# robotito.net
KiCad netlist of a schematic drawn in EAGLE
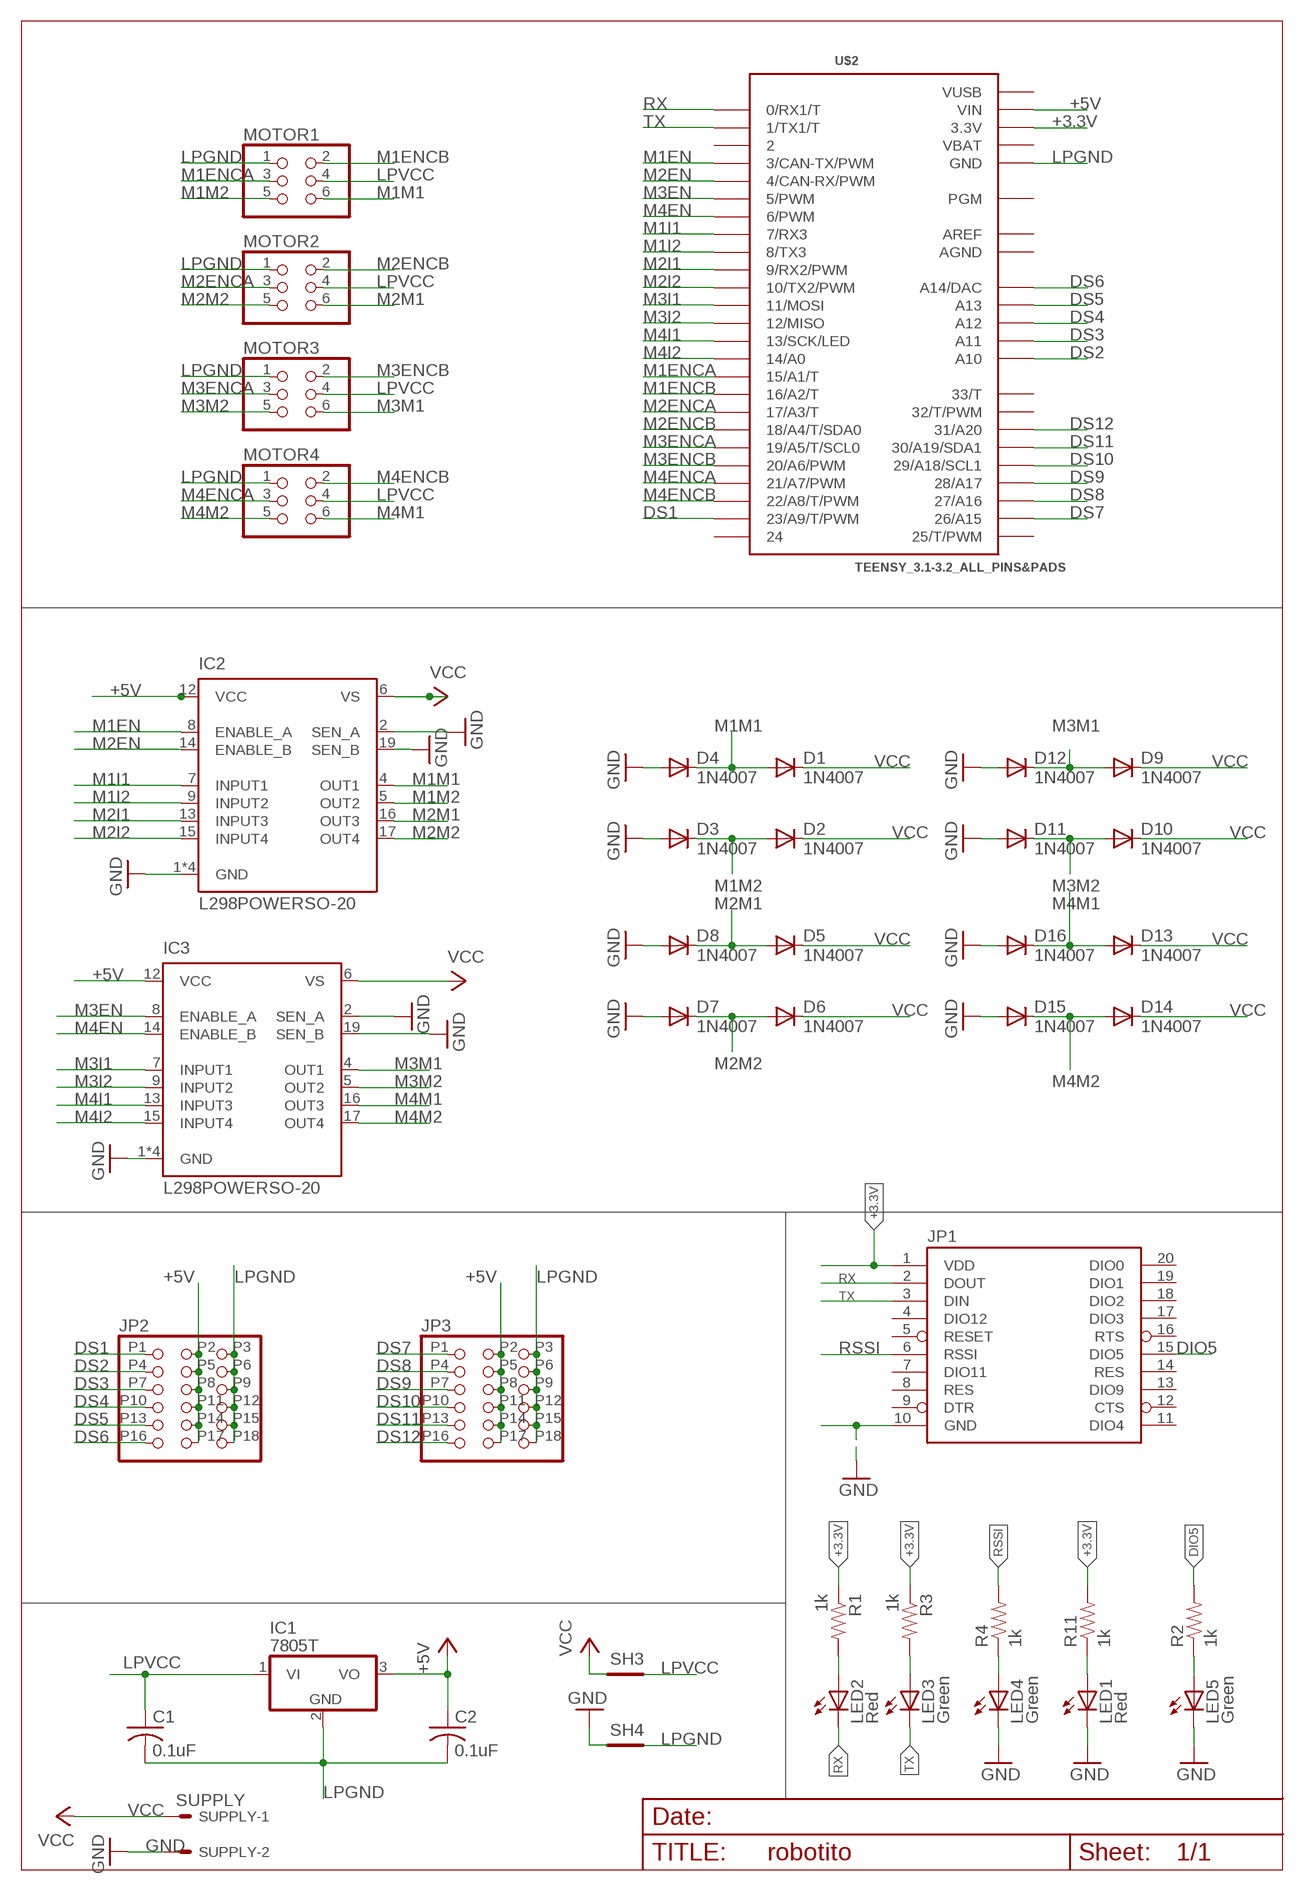
[diagram p0: schematic, sheet 1]

(export (version "E")
  (design (tool "Eeschema 10.0.6"))
  (components
    (comp (ref "C1")
      (value "0.1uF")
      (footprint "eagle-import:C0805")
      (libsource (lib "eagle-import") (part "C-USC0805"))
    )
    (comp (ref "C2")
      (value "0.1uF")
      (footprint "eagle-import:C0805")
      (libsource (lib "eagle-import") (part "C-USC0805"))
    )
    (comp (ref "D1")
      (value "1N4007")
      (footprint "eagle-import:DO41-10")
      (libsource (lib "eagle-import") (part "1N4004"))
    )
    (comp (ref "D2")
      (value "1N4007")
      (footprint "eagle-import:DO41-10")
      (libsource (lib "eagle-import") (part "1N4004"))
    )
    (comp (ref "D3")
      (value "1N4007")
      (footprint "eagle-import:DO41-10")
      (libsource (lib "eagle-import") (part "1N4004"))
    )
    (comp (ref "D4")
      (value "1N4007")
      (footprint "eagle-import:DO41-10")
      (libsource (lib "eagle-import") (part "1N4004"))
    )
    (comp (ref "D5")
      (value "1N4007")
      (footprint "eagle-import:DO41-10")
      (libsource (lib "eagle-import") (part "1N4004"))
    )
    (comp (ref "D6")
      (value "1N4007")
      (footprint "eagle-import:DO41-10")
      (libsource (lib "eagle-import") (part "1N4004"))
    )
    (comp (ref "D7")
      (value "1N4007")
      (footprint "eagle-import:DO41-10")
      (libsource (lib "eagle-import") (part "1N4004"))
    )
    (comp (ref "D8")
      (value "1N4007")
      (footprint "eagle-import:DO41-10")
      (libsource (lib "eagle-import") (part "1N4004"))
    )
    (comp (ref "D9")
      (value "1N4007")
      (footprint "eagle-import:DO41-10")
      (libsource (lib "eagle-import") (part "1N4004"))
    )
    (comp (ref "D10")
      (value "1N4007")
      (footprint "eagle-import:DO41-10")
      (libsource (lib "eagle-import") (part "1N4004"))
    )
    (comp (ref "D11")
      (value "1N4007")
      (footprint "eagle-import:DO41-10")
      (libsource (lib "eagle-import") (part "1N4004"))
    )
    (comp (ref "D12")
      (value "1N4007")
      (footprint "eagle-import:DO41-10")
      (libsource (lib "eagle-import") (part "1N4004"))
    )
    (comp (ref "D13")
      (value "1N4007")
      (footprint "eagle-import:DO41-10")
      (libsource (lib "eagle-import") (part "1N4004"))
    )
    (comp (ref "D14")
      (value "1N4007")
      (footprint "eagle-import:DO41-10")
      (libsource (lib "eagle-import") (part "1N4004"))
    )
    (comp (ref "D15")
      (value "1N4007")
      (footprint "eagle-import:DO41-10")
      (libsource (lib "eagle-import") (part "1N4004"))
    )
    (comp (ref "D16")
      (value "1N4007")
      (footprint "eagle-import:DO41-10")
      (libsource (lib "eagle-import") (part "1N4004"))
    )
    (comp (ref "IC1")
      (value "7805T")
      (footprint "eagle-import:TO220H")
      (libsource (lib "eagle-import") (part "78T05"))
    )
    (comp (ref "IC2")
      (value "L298POWERSO-20")
      (footprint "eagle-import:POWERSO-20")
      (libsource (lib "eagle-import") (part "L298POWERSO-20"))
    )
    (comp (ref "IC3")
      (value "L298POWERSO-20")
      (footprint "eagle-import:POWERSO-20")
      (libsource (lib "eagle-import") (part "L298POWERSO-20"))
    )
    (comp (ref "JP1")
      (value "XBEE-1B1")
      (footprint "eagle-import:XBEE-1")
      (libsource (lib "eagle-import") (part "XBEE-1B1"))
    )
    (comp (ref "JP2")
      (value "PINHD-2X6")
      (footprint "eagle-import:2X06")
      (libsource (lib "eagle-import") (part "PINHD-2X6"))
    )
    (comp (ref "JP3")
      (value "PINHD-2X6")
      (footprint "eagle-import:2X06")
      (libsource (lib "eagle-import") (part "PINHD-2X6"))
    )
    (comp (ref "LED1")
      (value "Red")
      (footprint "eagle-import:LED-0603")
      (libsource (lib "eagle-import") (part "LED-RED0603"))
    )
    (comp (ref "LED2")
      (value "Red")
      (footprint "eagle-import:LED-0603")
      (libsource (lib "eagle-import") (part "LED-RED0603"))
    )
    (comp (ref "LED3")
      (value "Green")
      (footprint "eagle-import:LED-0603")
      (libsource (lib "eagle-import") (part "LED-GREEN0603"))
    )
    (comp (ref "LED4")
      (value "Green")
      (footprint "eagle-import:LED-0603")
      (libsource (lib "eagle-import") (part "LED-GREEN0603"))
    )
    (comp (ref "LED5")
      (value "Green")
      (footprint "eagle-import:LED-0603")
      (libsource (lib "eagle-import") (part "LED-GREEN0603"))
    )
    (comp (ref "MOTOR1")
      (value "PINHD-2X3")
      (footprint "eagle-import:2X03")
      (libsource (lib "eagle-import") (part "PINHD-2X3"))
    )
    (comp (ref "MOTOR2")
      (value "PINHD-2X3")
      (footprint "eagle-import:2X03")
      (libsource (lib "eagle-import") (part "PINHD-2X3"))
    )
    (comp (ref "MOTOR3")
      (value "PINHD-2X3")
      (footprint "eagle-import:2X03")
      (libsource (lib "eagle-import") (part "PINHD-2X3"))
    )
    (comp (ref "MOTOR4")
      (value "PINHD-2X3")
      (footprint "eagle-import:2X03")
      (libsource (lib "eagle-import") (part "PINHD-2X3"))
    )
    (comp (ref "R1")
      (value "1k")
      (footprint "eagle-import:0603-RES")
      (libsource (lib "eagle-import") (part "1KOHM1/10W1%(0603)"))
    )
    (comp (ref "R2")
      (value "1k")
      (footprint "eagle-import:0603-RES")
      (libsource (lib "eagle-import") (part "1KOHM1/10W1%(0603)"))
    )
    (comp (ref "R3")
      (value "1k")
      (footprint "eagle-import:0603-RES")
      (libsource (lib "eagle-import") (part "1KOHM1/10W1%(0603)"))
    )
    (comp (ref "R4")
      (value "1k")
      (footprint "eagle-import:0603-RES")
      (libsource (lib "eagle-import") (part "1KOHM1/10W1%(0603)"))
    )
    (comp (ref "R11")
      (value "1k")
      (footprint "eagle-import:0603-RES")
      (libsource (lib "eagle-import") (part "1KOHM1/10W1%(0603)"))
    )
    (comp (ref "SH3")
      (value "SHORT-HT5")
      (footprint "eagle-import:SHORT_TOP-50")
      (libsource (lib "eagle-import") (part "SHORT-HT5"))
    )
    (comp (ref "SH4")
      (value "SHORT-HT5")
      (footprint "eagle-import:SHORT_TOP-50")
      (libsource (lib "eagle-import") (part "SHORT-HT5"))
    )
    (comp (ref "SUPPLY")
      (value "SUPPLY")
      (footprint "eagle-import:6410-02")
      (libsource (lib "eagle-import") (part "22-?-0227-2021"))
    )
    (comp (ref "U$2")
      (value "TEENSY_3.1-3.2_ALL_PINS&PADS")
      (footprint "eagle-import:TEENSY_3.0-3.2_ALL_PINS_&_PADS")
      (libsource (lib "eagle-import") (part "TEENSY_3.1-3.2_ALL_PINS&PADS"))
    )
  )
  (nets
    (net (code "1") (name "+3.3V") (class "Default")
      (node (ref "JP1") (pin "1") (pinfunction "VDD_1") (pintype "power_in"))
      (node (ref "R1") (pin "1") (pinfunction "1_1") (pintype "passive"))
      (node (ref "R11") (pin "2") (pinfunction "2_2") (pintype "passive"))
      (node (ref "R3") (pin "1") (pinfunction "1_1") (pintype "passive"))
      (node (ref "U$2") (pin "3.3V") (pinfunction "3.3V_3.3V") (pintype "power_in"))
      (node (ref "U$2") (pin "3.3V1") (pinfunction "3.3V_3.3V1") (pintype "power_in"))
      (node (ref "U$2") (pin "3.3V2") (pinfunction "3.3V_3.3V2") (pintype "power_in"))
    )
    (net (code "2") (name "+5V") (class "Default")
      (node (ref "C2") (pin "1") (pinfunction "1_1") (pintype "passive"))
      (node (ref "IC1") (pin "3") (pinfunction "VO_3") (pintype "passive"))
      (node (ref "IC2") (pin "12") (pinfunction "VCC_12") (pintype "power_in"))
      (node (ref "IC3") (pin "12") (pinfunction "VCC_12") (pintype "power_in"))
      (node (ref "JP2") (pin "P11") (pinfunction "P11_P11") (pintype "passive"))
      (node (ref "JP2") (pin "P14") (pinfunction "P14_P14") (pintype "passive"))
      (node (ref "JP2") (pin "P17") (pinfunction "P17_P17") (pintype "passive"))
      (node (ref "JP2") (pin "P2") (pinfunction "P2_P2") (pintype "passive"))
      (node (ref "JP2") (pin "P5") (pinfunction "P5_P5") (pintype "passive"))
      (node (ref "JP2") (pin "P8") (pinfunction "P8_P8") (pintype "passive"))
      (node (ref "JP3") (pin "P11") (pinfunction "P11_P11") (pintype "passive"))
      (node (ref "JP3") (pin "P14") (pinfunction "P14_P14") (pintype "passive"))
      (node (ref "JP3") (pin "P17") (pinfunction "P17_P17") (pintype "passive"))
      (node (ref "JP3") (pin "P2") (pinfunction "P2_P2") (pintype "passive"))
      (node (ref "JP3") (pin "P5") (pinfunction "P5_P5") (pintype "passive"))
      (node (ref "JP3") (pin "P8") (pinfunction "P8_P8") (pintype "passive"))
      (node (ref "U$2") (pin "VIN") (pinfunction "VIN_VIN") (pintype "power_in"))
    )
    (net (code "3") (name "/AGND") (class "Default")
      (node (ref "U$2") (pin "AGND") (pinfunction "AGND_AGND") (pintype "power_in"))
    )
    (net (code "4") (name "/AREF") (class "Default")
      (node (ref "U$2") (pin "AREF") (pinfunction "AREF_AREF") (pintype "power_in"))
    )
    (net (code "5") (name "/DS1") (class "Default")
      (node (ref "JP2") (pin "P1") (pinfunction "P1_P1") (pintype "passive"))
      (node (ref "U$2") (pin "23/A9") (pinfunction "23/A9/T/PWM_23/A9") (pintype "bidirectional"))
    )
    (net (code "6") (name "/DS2") (class "Default")
      (node (ref "JP2") (pin "P4") (pinfunction "P4_P4") (pintype "passive"))
      (node (ref "U$2") (pin "A10") (pinfunction "A10_A10") (pintype "bidirectional"))
    )
    (net (code "7") (name "/DS3") (class "Default")
      (node (ref "JP2") (pin "P7") (pinfunction "P7_P7") (pintype "passive"))
      (node (ref "U$2") (pin "A11") (pinfunction "A11_A11") (pintype "bidirectional"))
    )
    (net (code "8") (name "/DS4") (class "Default")
      (node (ref "JP2") (pin "P10") (pinfunction "P10_P10") (pintype "passive"))
      (node (ref "U$2") (pin "A12") (pinfunction "A12_A12") (pintype "bidirectional"))
    )
    (net (code "9") (name "/DS5") (class "Default")
      (node (ref "JP2") (pin "P13") (pinfunction "P13_P13") (pintype "passive"))
      (node (ref "U$2") (pin "A13") (pinfunction "A13_A13") (pintype "bidirectional"))
    )
    (net (code "10") (name "/DS6") (class "Default")
      (node (ref "JP2") (pin "P16") (pinfunction "P16_P16") (pintype "passive"))
      (node (ref "U$2") (pin "RESET/DAC") (pinfunction "A14/DAC_RESET/DAC") (pintype "bidirectional"))
    )
    (net (code "11") (name "/DS7") (class "Default")
      (node (ref "JP3") (pin "P1") (pinfunction "P1_P1") (pintype "passive"))
      (node (ref "U$2") (pin "26") (pinfunction "26/A15_26") (pintype "bidirectional"))
    )
    (net (code "12") (name "/DS8") (class "Default")
      (node (ref "JP3") (pin "P4") (pinfunction "P4_P4") (pintype "passive"))
      (node (ref "U$2") (pin "27") (pinfunction "27/A16_27") (pintype "bidirectional"))
    )
    (net (code "13") (name "/DS9") (class "Default")
      (node (ref "JP3") (pin "P7") (pinfunction "P7_P7") (pintype "passive"))
      (node (ref "U$2") (pin "28") (pinfunction "28/A17_28") (pintype "bidirectional"))
    )
    (net (code "14") (name "/DS10") (class "Default")
      (node (ref "JP3") (pin "P10") (pinfunction "P10_P10") (pintype "passive"))
      (node (ref "U$2") (pin "29") (pinfunction "29/A18/SCL1_29") (pintype "bidirectional"))
    )
    (net (code "15") (name "/DS11") (class "Default")
      (node (ref "JP3") (pin "P13") (pinfunction "P13_P13") (pintype "passive"))
      (node (ref "U$2") (pin "30") (pinfunction "30/A19/SDA1_30") (pintype "bidirectional"))
    )
    (net (code "16") (name "/DS12") (class "Default")
      (node (ref "JP3") (pin "P16") (pinfunction "P16_P16") (pintype "passive"))
      (node (ref "U$2") (pin "31") (pinfunction "31/A20_31") (pintype "bidirectional"))
    )
    (net (code "17") (name "/LPGND") (class "Default")
      (node (ref "C1") (pin "2") (pinfunction "2_2") (pintype "passive"))
      (node (ref "C2") (pin "2") (pinfunction "2_2") (pintype "passive"))
      (node (ref "IC1") (pin "2") (pinfunction "GND_2") (pintype "passive"))
      (node (ref "JP2") (pin "P12") (pinfunction "P12_P12") (pintype "passive"))
      (node (ref "JP2") (pin "P15") (pinfunction "P15_P15") (pintype "passive"))
      (node (ref "JP2") (pin "P18") (pinfunction "P18_P18") (pintype "passive"))
      (node (ref "JP2") (pin "P3") (pinfunction "P3_P3") (pintype "passive"))
      (node (ref "JP2") (pin "P6") (pinfunction "P6_P6") (pintype "passive"))
      (node (ref "JP2") (pin "P9") (pinfunction "P9_P9") (pintype "passive"))
      (node (ref "JP3") (pin "P12") (pinfunction "P12_P12") (pintype "passive"))
      (node (ref "JP3") (pin "P15") (pinfunction "P15_P15") (pintype "passive"))
      (node (ref "JP3") (pin "P18") (pinfunction "P18_P18") (pintype "passive"))
      (node (ref "JP3") (pin "P3") (pinfunction "P3_P3") (pintype "passive"))
      (node (ref "JP3") (pin "P6") (pinfunction "P6_P6") (pintype "passive"))
      (node (ref "JP3") (pin "P9") (pinfunction "P9_P9") (pintype "passive"))
      (node (ref "MOTOR1") (pin "1") (pinfunction "1_1") (pintype "passive"))
      (node (ref "MOTOR2") (pin "1") (pinfunction "1_1") (pintype "passive"))
      (node (ref "MOTOR3") (pin "1") (pinfunction "1_1") (pintype "passive"))
      (node (ref "MOTOR4") (pin "1") (pinfunction "1_1") (pintype "passive"))
      (node (ref "SH4") (pin "2") (pinfunction "P$2_2") (pintype "bidirectional"))
      (node (ref "U$2") (pin "GND") (pinfunction "GND_GND") (pintype "power_in"))
      (node (ref "U$2") (pin "GND1") (pinfunction "GND_GND1") (pintype "power_in"))
      (node (ref "U$2") (pin "GND2") (pinfunction "GND_GND2") (pintype "power_in"))
    )
    (net (code "18") (name "/LPVCC") (class "Default")
      (node (ref "C1") (pin "1") (pinfunction "1_1") (pintype "passive"))
      (node (ref "IC1") (pin "1") (pinfunction "VI_1") (pintype "input"))
      (node (ref "MOTOR1") (pin "4") (pinfunction "4_4") (pintype "passive"))
      (node (ref "MOTOR2") (pin "4") (pinfunction "4_4") (pintype "passive"))
      (node (ref "MOTOR3") (pin "4") (pinfunction "4_4") (pintype "passive"))
      (node (ref "MOTOR4") (pin "4") (pinfunction "4_4") (pintype "passive"))
      (node (ref "SH3") (pin "2") (pinfunction "P$2_2") (pintype "bidirectional"))
    )
    (net (code "19") (name "/M1EN") (class "Default")
      (node (ref "IC2") (pin "8") (pinfunction "ENABLE_A_8") (pintype "input"))
      (node (ref "U$2") (pin "3") (pinfunction "3/CAN-TX/PWM_3") (pintype "bidirectional"))
    )
    (net (code "20") (name "/M1ENCA") (class "Default")
      (node (ref "MOTOR1") (pin "3") (pinfunction "3_3") (pintype "passive"))
      (node (ref "U$2") (pin "15/A1") (pinfunction "15/A1/T_15/A1") (pintype "bidirectional"))
    )
    (net (code "21") (name "/M1ENCB") (class "Default")
      (node (ref "MOTOR1") (pin "2") (pinfunction "2_2") (pintype "passive"))
      (node (ref "U$2") (pin "16/A2") (pinfunction "16/A2/T_16/A2") (pintype "bidirectional"))
    )
    (net (code "22") (name "/M1I1") (class "Default")
      (node (ref "IC2") (pin "7") (pinfunction "INPUT1_7") (pintype "input"))
      (node (ref "U$2") (pin "7") (pinfunction "7/RX3_7") (pintype "bidirectional"))
    )
    (net (code "23") (name "/M1I2") (class "Default")
      (node (ref "IC2") (pin "9") (pinfunction "INPUT2_9") (pintype "input"))
      (node (ref "U$2") (pin "8") (pinfunction "8/TX3_8") (pintype "bidirectional"))
    )
    (net (code "24") (name "/M1M1") (class "Default")
      (node (ref "D1") (pin "A") (pinfunction "A_A") (pintype "passive"))
      (node (ref "D4") (pin "C") (pinfunction "C_C") (pintype "passive"))
      (node (ref "IC2") (pin "4") (pinfunction "OUT1_4") (pintype "output"))
      (node (ref "MOTOR1") (pin "6") (pinfunction "6_6") (pintype "passive"))
    )
    (net (code "25") (name "/M1M2") (class "Default")
      (node (ref "D2") (pin "A") (pinfunction "A_A") (pintype "passive"))
      (node (ref "D3") (pin "C") (pinfunction "C_C") (pintype "passive"))
      (node (ref "IC2") (pin "5") (pinfunction "OUT2_5") (pintype "output"))
      (node (ref "MOTOR1") (pin "5") (pinfunction "5_5") (pintype "passive"))
    )
    (net (code "26") (name "/M2EN") (class "Default")
      (node (ref "IC2") (pin "14") (pinfunction "ENABLE_B_14") (pintype "input"))
      (node (ref "U$2") (pin "4") (pinfunction "4/CAN-RX/PWM_4") (pintype "bidirectional"))
    )
    (net (code "27") (name "/M2ENCA") (class "Default")
      (node (ref "MOTOR2") (pin "3") (pinfunction "3_3") (pintype "passive"))
      (node (ref "U$2") (pin "17/A3") (pinfunction "17/A3/T_17/A3") (pintype "bidirectional"))
    )
    (net (code "28") (name "/M2ENCB") (class "Default")
      (node (ref "MOTOR2") (pin "2") (pinfunction "2_2") (pintype "passive"))
      (node (ref "U$2") (pin "18/A4") (pinfunction "18/A4/T/SDA0_18/A4") (pintype "bidirectional"))
    )
    (net (code "29") (name "/M2I1") (class "Default")
      (node (ref "IC2") (pin "13") (pinfunction "INPUT3_13") (pintype "input"))
      (node (ref "U$2") (pin "9") (pinfunction "9/RX2/PWM_9") (pintype "bidirectional"))
    )
    (net (code "30") (name "/M2I2") (class "Default")
      (node (ref "IC2") (pin "15") (pinfunction "INPUT4_15") (pintype "input"))
      (node (ref "U$2") (pin "10") (pinfunction "10/TX2/PWM_10") (pintype "bidirectional"))
    )
    (net (code "31") (name "/M2M1") (class "Default")
      (node (ref "D5") (pin "A") (pinfunction "A_A") (pintype "passive"))
      (node (ref "D8") (pin "C") (pinfunction "C_C") (pintype "passive"))
      (node (ref "IC2") (pin "16") (pinfunction "OUT3_16") (pintype "output"))
      (node (ref "MOTOR2") (pin "6") (pinfunction "6_6") (pintype "passive"))
    )
    (net (code "32") (name "/M2M2") (class "Default")
      (node (ref "D6") (pin "A") (pinfunction "A_A") (pintype "passive"))
      (node (ref "D7") (pin "C") (pinfunction "C_C") (pintype "passive"))
      (node (ref "IC2") (pin "17") (pinfunction "OUT4_17") (pintype "output"))
      (node (ref "MOTOR2") (pin "5") (pinfunction "5_5") (pintype "passive"))
    )
    (net (code "33") (name "/M3EN") (class "Default")
      (node (ref "IC3") (pin "8") (pinfunction "ENABLE_A_8") (pintype "input"))
      (node (ref "U$2") (pin "5") (pinfunction "5/PWM_5") (pintype "bidirectional"))
    )
    (net (code "34") (name "/M3ENCA") (class "Default")
      (node (ref "MOTOR3") (pin "3") (pinfunction "3_3") (pintype "passive"))
      (node (ref "U$2") (pin "19/A5") (pinfunction "19/A5/T/SCL0_19/A5") (pintype "bidirectional"))
    )
    (net (code "35") (name "/M3ENCB") (class "Default")
      (node (ref "MOTOR3") (pin "2") (pinfunction "2_2") (pintype "passive"))
      (node (ref "U$2") (pin "20/A6") (pinfunction "20/A6/PWM_20/A6") (pintype "bidirectional"))
    )
    (net (code "36") (name "/M3I1") (class "Default")
      (node (ref "IC3") (pin "7") (pinfunction "INPUT1_7") (pintype "input"))
      (node (ref "U$2") (pin "11") (pinfunction "11/MOSI_11") (pintype "bidirectional"))
    )
    (net (code "37") (name "/M3I2") (class "Default")
      (node (ref "IC3") (pin "9") (pinfunction "INPUT2_9") (pintype "input"))
      (node (ref "U$2") (pin "12") (pinfunction "12/MISO_12") (pintype "bidirectional"))
    )
    (net (code "38") (name "/M3M1") (class "Default")
      (node (ref "D12") (pin "C") (pinfunction "C_C") (pintype "passive"))
      (node (ref "D9") (pin "A") (pinfunction "A_A") (pintype "passive"))
      (node (ref "IC3") (pin "4") (pinfunction "OUT1_4") (pintype "output"))
      (node (ref "MOTOR3") (pin "6") (pinfunction "6_6") (pintype "passive"))
    )
    (net (code "39") (name "/M3M2") (class "Default")
      (node (ref "D10") (pin "A") (pinfunction "A_A") (pintype "passive"))
      (node (ref "D11") (pin "C") (pinfunction "C_C") (pintype "passive"))
      (node (ref "IC3") (pin "5") (pinfunction "OUT2_5") (pintype "output"))
      (node (ref "MOTOR3") (pin "5") (pinfunction "5_5") (pintype "passive"))
    )
    (net (code "40") (name "/M4EN") (class "Default")
      (node (ref "IC3") (pin "14") (pinfunction "ENABLE_B_14") (pintype "input"))
      (node (ref "U$2") (pin "6") (pinfunction "6/PWM_6") (pintype "bidirectional"))
    )
    (net (code "41") (name "/M4ENCA") (class "Default")
      (node (ref "MOTOR4") (pin "3") (pinfunction "3_3") (pintype "passive"))
      (node (ref "U$2") (pin "21/A7") (pinfunction "21/A7/PWM_21/A7") (pintype "bidirectional"))
    )
    (net (code "42") (name "/M4ENCB") (class "Default")
      (node (ref "MOTOR4") (pin "2") (pinfunction "2_2") (pintype "passive"))
      (node (ref "U$2") (pin "22/A8") (pinfunction "22/A8/T/PWM_22/A8") (pintype "bidirectional"))
    )
    (net (code "43") (name "/M4I1") (class "Default")
      (node (ref "IC3") (pin "13") (pinfunction "INPUT3_13") (pintype "input"))
      (node (ref "U$2") (pin "13") (pinfunction "13/SCK/LED_13") (pintype "bidirectional"))
    )
    (net (code "44") (name "/M4I2") (class "Default")
      (node (ref "IC3") (pin "15") (pinfunction "INPUT4_15") (pintype "input"))
      (node (ref "U$2") (pin "14/A0") (pinfunction "14/A0_14/A0") (pintype "bidirectional"))
    )
    (net (code "45") (name "/M4M1") (class "Default")
      (node (ref "D13") (pin "A") (pinfunction "A_A") (pintype "passive"))
      (node (ref "D16") (pin "C") (pinfunction "C_C") (pintype "passive"))
      (node (ref "IC3") (pin "16") (pinfunction "OUT3_16") (pintype "output"))
      (node (ref "MOTOR4") (pin "6") (pinfunction "6_6") (pintype "passive"))
    )
    (net (code "46") (name "/M4M2") (class "Default")
      (node (ref "D14") (pin "A") (pinfunction "A_A") (pintype "passive"))
      (node (ref "D15") (pin "C") (pinfunction "C_C") (pintype "passive"))
      (node (ref "IC3") (pin "17") (pinfunction "OUT4_17") (pintype "output"))
      (node (ref "MOTOR4") (pin "5") (pinfunction "5_5") (pintype "passive"))
    )
    (net (code "47") (name "/VBAT") (class "Default")
      (node (ref "U$2") (pin "VBAT") (pinfunction "VBAT_VBAT") (pintype "power_in"))
    )
    (net (code "48") (name "/VUSB") (class "Default")
      (node (ref "U$2") (pin "VUSB") (pinfunction "VUSB_VUSB") (pintype "power_in"))
    )
    (net (code "49") (name "DIO5") (class "Default")
      (node (ref "JP1") (pin "15") (pinfunction "DIO5_15") (pintype "bidirectional"))
      (node (ref "R2") (pin "2") (pinfunction "2_2") (pintype "passive"))
    )
    (net (code "50") (name "GND") (class "Default")
      (node (ref "D11") (pin "A") (pinfunction "A_A") (pintype "passive"))
      (node (ref "D12") (pin "A") (pinfunction "A_A") (pintype "passive"))
      (node (ref "D15") (pin "A") (pinfunction "A_A") (pintype "passive"))
      (node (ref "D16") (pin "A") (pinfunction "A_A") (pintype "passive"))
      (node (ref "D3") (pin "A") (pinfunction "A_A") (pintype "passive"))
      (node (ref "D4") (pin "A") (pinfunction "A_A") (pintype "passive"))
      (node (ref "D7") (pin "A") (pinfunction "A_A") (pintype "passive"))
      (node (ref "D8") (pin "A") (pinfunction "A_A") (pintype "passive"))
      (node (ref "IC2") (pin "1") (pinfunction "GND_1") (pintype "power_in"))
      (node (ref "IC2") (pin "10") (pinfunction "GND_10") (pintype "power_in"))
      (node (ref "IC2") (pin "11") (pinfunction "GND_11") (pintype "power_in"))
      (node (ref "IC2") (pin "19") (pinfunction "SEN_B_19") (pintype "input"))
      (node (ref "IC2") (pin "2") (pinfunction "SEN_A_2") (pintype "input"))
      (node (ref "IC2") (pin "20") (pinfunction "GND_20") (pintype "power_in"))
      (node (ref "IC3") (pin "1") (pinfunction "GND_1") (pintype "power_in"))
      (node (ref "IC3") (pin "10") (pinfunction "GND_10") (pintype "power_in"))
      (node (ref "IC3") (pin "11") (pinfunction "GND_11") (pintype "power_in"))
      (node (ref "IC3") (pin "19") (pinfunction "SEN_B_19") (pintype "input"))
      (node (ref "IC3") (pin "2") (pinfunction "SEN_A_2") (pintype "input"))
      (node (ref "IC3") (pin "20") (pinfunction "GND_20") (pintype "power_in"))
      (node (ref "JP1") (pin "10") (pinfunction "GND_10") (pintype "power_in"))
      (node (ref "LED1") (pin "C") (pinfunction "C_C") (pintype "passive"))
      (node (ref "LED4") (pin "C") (pinfunction "C_C") (pintype "passive"))
      (node (ref "LED5") (pin "C") (pinfunction "C_C") (pintype "passive"))
      (node (ref "SH4") (pin "1") (pinfunction "P$1_1") (pintype "bidirectional"))
      (node (ref "SUPPLY") (pin "2") (pinfunction "S_2") (pintype "passive"))
    )
    (net (code "51") (name "Net-(LED1-PadA)") (class "Default")
      (node (ref "LED1") (pin "A") (pinfunction "A_A") (pintype "passive"))
      (node (ref "R11") (pin "1") (pinfunction "1_1") (pintype "passive"))
    )
    (net (code "52") (name "Net-(LED2-PadA)") (class "Default")
      (node (ref "LED2") (pin "A") (pinfunction "A_A") (pintype "passive"))
      (node (ref "R1") (pin "2") (pinfunction "2_2") (pintype "passive"))
    )
    (net (code "53") (name "Net-(LED3-PadA)") (class "Default")
      (node (ref "LED3") (pin "A") (pinfunction "A_A") (pintype "passive"))
      (node (ref "R3") (pin "2") (pinfunction "2_2") (pintype "passive"))
    )
    (net (code "54") (name "Net-(LED4-PadA)") (class "Default")
      (node (ref "LED4") (pin "A") (pinfunction "A_A") (pintype "passive"))
      (node (ref "R4") (pin "1") (pinfunction "1_1") (pintype "passive"))
    )
    (net (code "55") (name "Net-(LED5-PadA)") (class "Default")
      (node (ref "LED5") (pin "A") (pinfunction "A_A") (pintype "passive"))
      (node (ref "R2") (pin "1") (pinfunction "1_1") (pintype "passive"))
    )
    (net (code "56") (name "RSSI") (class "Default")
      (node (ref "JP1") (pin "6") (pinfunction "RSSI_6") (pintype "bidirectional"))
      (node (ref "R4") (pin "2") (pinfunction "2_2") (pintype "passive"))
    )
    (net (code "57") (name "RX") (class "Default")
      (node (ref "JP1") (pin "2") (pinfunction "DOUT_2") (pintype "output"))
      (node (ref "LED2") (pin "C") (pinfunction "C_C") (pintype "passive"))
      (node (ref "U$2") (pin "0") (pinfunction "0/RX1/T_0") (pintype "bidirectional"))
    )
    (net (code "58") (name "TX") (class "Default")
      (node (ref "JP1") (pin "3") (pinfunction "DIN_3") (pintype "input"))
      (node (ref "LED3") (pin "C") (pinfunction "C_C") (pintype "passive"))
      (node (ref "U$2") (pin "1") (pinfunction "1/TX1/T_1") (pintype "bidirectional"))
    )
    (net (code "59") (name "VCC") (class "Default")
      (node (ref "D1") (pin "C") (pinfunction "C_C") (pintype "passive"))
      (node (ref "D10") (pin "C") (pinfunction "C_C") (pintype "passive"))
      (node (ref "D13") (pin "C") (pinfunction "C_C") (pintype "passive"))
      (node (ref "D14") (pin "C") (pinfunction "C_C") (pintype "passive"))
      (node (ref "D2") (pin "C") (pinfunction "C_C") (pintype "passive"))
      (node (ref "D5") (pin "C") (pinfunction "C_C") (pintype "passive"))
      (node (ref "D6") (pin "C") (pinfunction "C_C") (pintype "passive"))
      (node (ref "D9") (pin "C") (pinfunction "C_C") (pintype "passive"))
      (node (ref "IC2") (pin "6") (pinfunction "VS_6") (pintype "power_in"))
      (node (ref "IC3") (pin "6") (pinfunction "VS_6") (pintype "power_in"))
      (node (ref "SH3") (pin "1") (pinfunction "P$1_1") (pintype "bidirectional"))
      (node (ref "SUPPLY") (pin "1") (pinfunction "S_1") (pintype "passive"))
    )
    (net (code "60") (name "unconnected-(JP1-CTS-Pad12)") (class "Default")
      (node (ref "JP1") (pin "12") (pinfunction "CTS_12") (pintype "output"))
    )
    (net (code "61") (name "unconnected-(JP1-DIO0-Pad20)") (class "Default")
      (node (ref "JP1") (pin "20") (pinfunction "DIO0_20") (pintype "bidirectional"))
    )
    (net (code "62") (name "unconnected-(JP1-DIO1-Pad19)") (class "Default")
      (node (ref "JP1") (pin "19") (pinfunction "DIO1_19") (pintype "bidirectional"))
    )
    (net (code "63") (name "unconnected-(JP1-DIO2-Pad18)") (class "Default")
      (node (ref "JP1") (pin "18") (pinfunction "DIO2_18") (pintype "bidirectional"))
    )
    (net (code "64") (name "unconnected-(JP1-DIO3-Pad17)") (class "Default")
      (node (ref "JP1") (pin "17") (pinfunction "DIO3_17") (pintype "bidirectional"))
    )
    (net (code "65") (name "unconnected-(JP1-DIO4-Pad11)") (class "Default")
      (node (ref "JP1") (pin "11") (pinfunction "DIO4_11") (pintype "bidirectional"))
    )
    (net (code "66") (name "unconnected-(JP1-DIO9-Pad13)") (class "Default")
      (node (ref "JP1") (pin "13") (pinfunction "DIO9_13") (pintype "bidirectional"))
    )
    (net (code "67") (name "unconnected-(JP1-DIO11-Pad7)") (class "Default")
      (node (ref "JP1") (pin "7") (pinfunction "DIO11_7") (pintype "bidirectional"))
    )
    (net (code "68") (name "unconnected-(JP1-DIO12-Pad4)") (class "Default")
      (node (ref "JP1") (pin "4") (pinfunction "DIO12_4") (pintype "bidirectional"))
    )
    (net (code "69") (name "unconnected-(JP1-DTR-Pad9)") (class "Default")
      (node (ref "JP1") (pin "9") (pinfunction "DTR_9") (pintype "bidirectional"))
    )
    (net (code "70") (name "unconnected-(JP1-RES-Pad8)") (class "Default")
      (node (ref "JP1") (pin "8") (pinfunction "RES_8") (pintype "bidirectional"))
    )
    (net (code "71") (name "unconnected-(JP1-RES-Pad14)") (class "Default")
      (node (ref "JP1") (pin "14") (pinfunction "RES_14") (pintype "bidirectional"))
    )
    (net (code "72") (name "unconnected-(JP1-RESET-Pad5)") (class "Default")
      (node (ref "JP1") (pin "5") (pinfunction "RESET_5") (pintype "input"))
    )
    (net (code "73") (name "unconnected-(JP1-RTS-Pad16)") (class "Default")
      (node (ref "JP1") (pin "16") (pinfunction "RTS_16") (pintype "input"))
    )
    (net (code "74") (name "unconnected-(U$2-25{slash}T{slash}PWM-Pad25)") (class "Default")
      (node (ref "U$2") (pin "25") (pinfunction "25/T/PWM_25") (pintype "bidirectional"))
    )
    (net (code "75") (name "unconnected-(U$2-32{slash}T{slash}PWM-Pad32)") (class "Default")
      (node (ref "U$2") (pin "32") (pinfunction "32/T/PWM_32") (pintype "bidirectional"))
    )
    (net (code "76") (name "unconnected-(U$2-33{slash}T-Pad33)") (class "Default")
      (node (ref "U$2") (pin "33") (pinfunction "33/T_33") (pintype "bidirectional"))
    )
    (net (code "77") (name "unconnected-(U$2-Pad2)") (class "Default")
      (node (ref "U$2") (pin "2") (pinfunction "2_2") (pintype "bidirectional"))
    )
    (net (code "78") (name "unconnected-(U$2-Pad24)") (class "Default")
      (node (ref "U$2") (pin "24") (pinfunction "24_24") (pintype "bidirectional"))
    )
    (net (code "79") (name "unconnected-(U$2-PadPGM)") (class "Default")
      (node (ref "U$2") (pin "PGM") (pinfunction "PGM_PGM") (pintype "bidirectional"))
    )
  )
)
